# signal-a-2.net
KiCad netlist of a schematic drawn in EAGLE
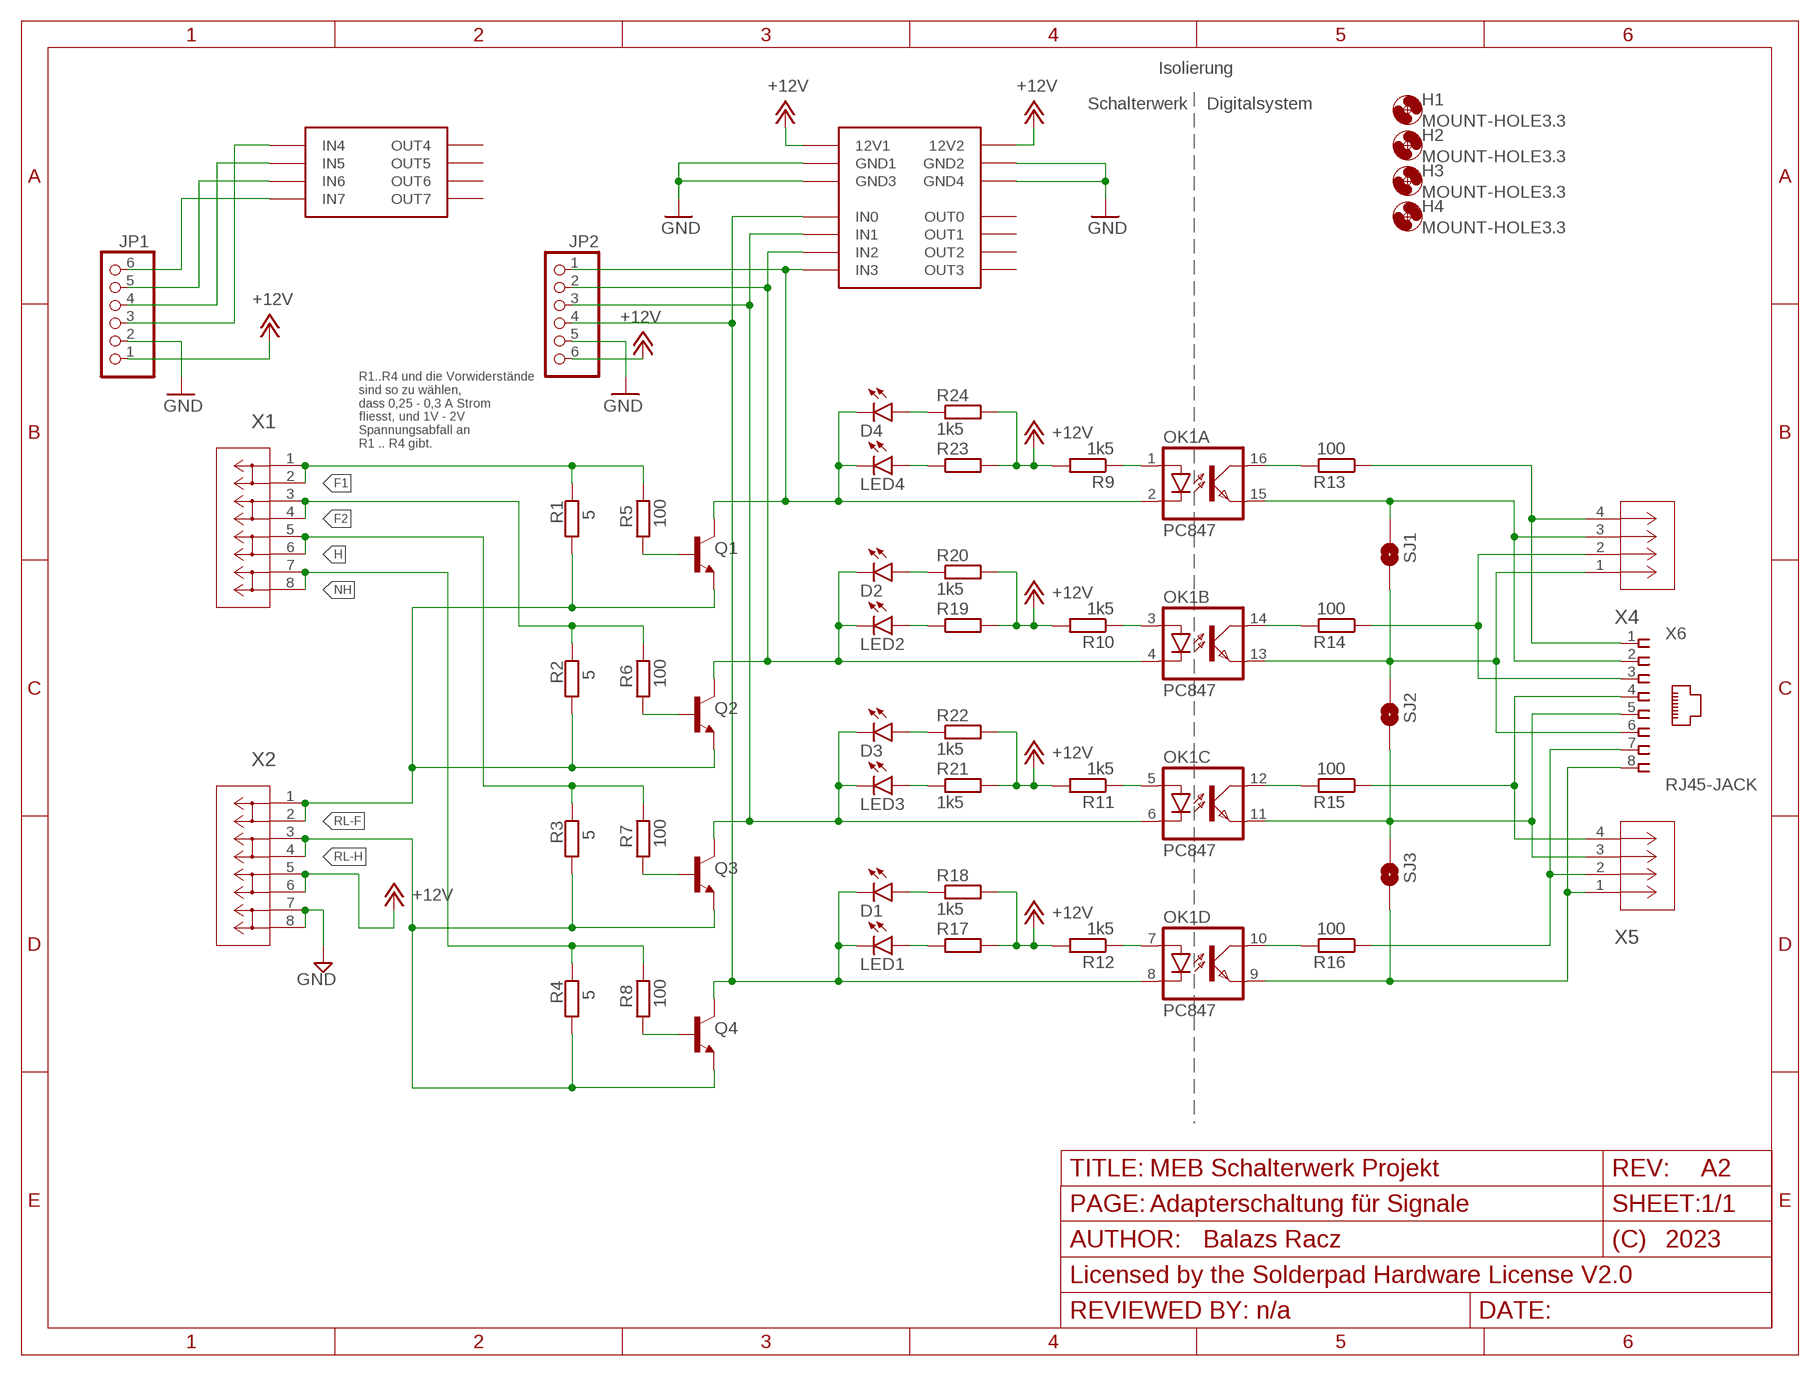
[diagram p0: schematic, sheet 1]

(export (version "E")
  (design (tool "Eeschema 10.0.6"))
  (components
    (comp (ref "D1")
      (value "LEDHEADER")
      (footprint "eagle-import:LEDHEADER")
      (libsource (lib "eagle-import") (part "LEDHEADER"))
    )
    (comp (ref "D2")
      (value "LEDHEADER")
      (footprint "eagle-import:LEDHEADER")
      (libsource (lib "eagle-import") (part "LEDHEADER"))
    )
    (comp (ref "D3")
      (value "LEDHEADER")
      (footprint "eagle-import:LEDHEADER")
      (libsource (lib "eagle-import") (part "LEDHEADER"))
    )
    (comp (ref "D4")
      (value "LEDHEADER")
      (footprint "eagle-import:LEDHEADER")
      (libsource (lib "eagle-import") (part "LEDHEADER"))
    )
    (comp (ref "H1")
      (value "MOUNT-HOLE3.3")
      (footprint "eagle-import:3,3")
      (libsource (lib "eagle-import") (part "MOUNT-HOLE3.3"))
    )
    (comp (ref "H2")
      (value "MOUNT-HOLE3.3")
      (footprint "eagle-import:3,3")
      (libsource (lib "eagle-import") (part "MOUNT-HOLE3.3"))
    )
    (comp (ref "H3")
      (value "MOUNT-HOLE3.3")
      (footprint "eagle-import:3,3")
      (libsource (lib "eagle-import") (part "MOUNT-HOLE3.3"))
    )
    (comp (ref "H4")
      (value "MOUNT-HOLE3.3")
      (footprint "eagle-import:3,3")
      (libsource (lib "eagle-import") (part "MOUNT-HOLE3.3"))
    )
    (comp (ref "JP1")
      (value "PINHD-1X6-EDGE")
      (footprint "eagle-import:1X06")
      (libsource (lib "eagle-import") (part "PINHD-1X6-EDGE"))
    )
    (comp (ref "JP2")
      (value "PINHD-1X6-EDGE")
      (footprint "eagle-import:1X06")
      (libsource (lib "eagle-import") (part "PINHD-1X6-EDGE"))
    )
    (comp (ref "LED1")
      (value "LEDCHIPLED_0603")
      (footprint "eagle-import:CHIPLED_0603")
      (libsource (lib "eagle-import") (part "LEDCHIPLED_0603"))
    )
    (comp (ref "LED2")
      (value "LEDCHIPLED_0603")
      (footprint "eagle-import:CHIPLED_0603")
      (libsource (lib "eagle-import") (part "LEDCHIPLED_0603"))
    )
    (comp (ref "LED3")
      (value "LEDCHIPLED_0603")
      (footprint "eagle-import:CHIPLED_0603")
      (libsource (lib "eagle-import") (part "LEDCHIPLED_0603"))
    )
    (comp (ref "LED4")
      (value "LEDCHIPLED_0603")
      (footprint "eagle-import:CHIPLED_0603")
      (libsource (lib "eagle-import") (part "LEDCHIPLED_0603"))
    )
    (comp (ref "OK1")
      (value "PC847")
      (footprint "eagle-import:DIL16")
      (libsource (lib "eagle-import") (part "PC847"))
    )
    (comp (ref "Q1")
      (value "NPN-23")
      (footprint "eagle-import:SOT23")
      (libsource (lib "eagle-import") (part "NPN-23"))
    )
    (comp (ref "Q2")
      (value "NPN-23")
      (footprint "eagle-import:SOT23")
      (libsource (lib "eagle-import") (part "NPN-23"))
    )
    (comp (ref "Q3")
      (value "NPN-23")
      (footprint "eagle-import:SOT23")
      (libsource (lib "eagle-import") (part "NPN-23"))
    )
    (comp (ref "Q4")
      (value "NPN-23")
      (footprint "eagle-import:SOT23")
      (libsource (lib "eagle-import") (part "NPN-23"))
    )
    (comp (ref "R1")
      (value "5")
      (footprint "eagle-import:0617_22")
      (libsource (lib "eagle-import") (part "R-EU_0617/22"))
    )
    (comp (ref "R2")
      (value "5")
      (footprint "eagle-import:0617_22")
      (libsource (lib "eagle-import") (part "R-EU_0617/22"))
    )
    (comp (ref "R3")
      (value "5")
      (footprint "eagle-import:0617_22")
      (libsource (lib "eagle-import") (part "R-EU_0617/22"))
    )
    (comp (ref "R4")
      (value "5")
      (footprint "eagle-import:0617_22")
      (libsource (lib "eagle-import") (part "R-EU_0617/22"))
    )
    (comp (ref "R5")
      (value "100")
      (footprint "eagle-import:R0805")
      (libsource (lib "eagle-import") (part "R-EU_R0805"))
    )
    (comp (ref "R6")
      (value "100")
      (footprint "eagle-import:R0805")
      (libsource (lib "eagle-import") (part "R-EU_R0805"))
    )
    (comp (ref "R7")
      (value "100")
      (footprint "eagle-import:R0805")
      (libsource (lib "eagle-import") (part "R-EU_R0805"))
    )
    (comp (ref "R8")
      (value "100")
      (footprint "eagle-import:R0805")
      (libsource (lib "eagle-import") (part "R-EU_R0805"))
    )
    (comp (ref "R9")
      (value "1k5")
      (footprint "eagle-import:R0805")
      (libsource (lib "eagle-import") (part "R-EU_R0805"))
    )
    (comp (ref "R10")
      (value "1k5")
      (footprint "eagle-import:R0805")
      (libsource (lib "eagle-import") (part "R-EU_R0805"))
    )
    (comp (ref "R11")
      (value "1k5")
      (footprint "eagle-import:R0805")
      (libsource (lib "eagle-import") (part "R-EU_R0805"))
    )
    (comp (ref "R12")
      (value "1k5")
      (footprint "eagle-import:R0805")
      (libsource (lib "eagle-import") (part "R-EU_R0805"))
    )
    (comp (ref "R13")
      (value "100")
      (footprint "eagle-import:R0805")
      (libsource (lib "eagle-import") (part "R-EU_R0805"))
    )
    (comp (ref "R14")
      (value "100")
      (footprint "eagle-import:R0805")
      (libsource (lib "eagle-import") (part "R-EU_R0805"))
    )
    (comp (ref "R15")
      (value "100")
      (footprint "eagle-import:R0805")
      (libsource (lib "eagle-import") (part "R-EU_R0805"))
    )
    (comp (ref "R16")
      (value "100")
      (footprint "eagle-import:R0805")
      (libsource (lib "eagle-import") (part "R-EU_R0805"))
    )
    (comp (ref "R17")
      (value "1k5")
      (footprint "eagle-import:R0805")
      (libsource (lib "eagle-import") (part "R-EU_R0805"))
    )
    (comp (ref "R18")
      (value "1k5")
      (footprint "eagle-import:R0805")
      (libsource (lib "eagle-import") (part "R-EU_R0805"))
    )
    (comp (ref "R19")
      (value "1k5")
      (footprint "eagle-import:R0805")
      (libsource (lib "eagle-import") (part "R-EU_R0805"))
    )
    (comp (ref "R20")
      (value "1k5")
      (footprint "eagle-import:R0805")
      (libsource (lib "eagle-import") (part "R-EU_R0805"))
    )
    (comp (ref "R21")
      (value "1k5")
      (footprint "eagle-import:R0805")
      (libsource (lib "eagle-import") (part "R-EU_R0805"))
    )
    (comp (ref "R22")
      (value "1k5")
      (footprint "eagle-import:R0805")
      (libsource (lib "eagle-import") (part "R-EU_R0805"))
    )
    (comp (ref "R23")
      (value "1k5")
      (footprint "eagle-import:R0805")
      (libsource (lib "eagle-import") (part "R-EU_R0805"))
    )
    (comp (ref "R24")
      (value "1k5")
      (footprint "eagle-import:R0805")
      (libsource (lib "eagle-import") (part "R-EU_R0805"))
    )
    (comp (ref "SJ1")
      (value "SJRND2")
      (footprint "eagle-import:SJ_RND2")
      (libsource (lib "eagle-import") (part "SJRND2"))
    )
    (comp (ref "SJ2")
      (value "SJRND2")
      (footprint "eagle-import:SJ_RND2")
      (libsource (lib "eagle-import") (part "SJRND2"))
    )
    (comp (ref "SJ3")
      (value "SJRND2")
      (footprint "eagle-import:SJ_RND2")
      (libsource (lib "eagle-import") (part "SJRND2"))
    )
    (comp (ref "X1")
      (value "PHNX_4P_508CONN_1017493")
      (footprint "eagle-import:PHNX_4P_508")
      (fields
        (field (name "MANUFACTURER_PART_NUMBER") "1017505")
        (field (name "COPYRIGHT") "Copyright (C) 2023 Ultra Librarian. All rights reserved.")
      )
      (libsource (lib "eagle-import") (part "PHNX_4P_508CONN_1017493"))
    )
    (comp (ref "X2")
      (value "PHNX_4P_508CONN_1017493")
      (footprint "eagle-import:PHNX_4P_508")
      (fields
        (field (name "MANUFACTURER_PART_NUMBER") "1017505")
        (field (name "COPYRIGHT") "Copyright (C) 2023 Ultra Librarian. All rights reserved.")
      )
      (libsource (lib "eagle-import") (part "PHNX_4P_508CONN_1017493"))
    )
    (comp (ref "X3")
      (value "IO-HAT")
      (footprint "eagle-import:IOBOARD")
      (libsource (lib "eagle-import") (part "IO-HAT"))
    )
    (comp (ref "X4")
      (value "PHNX_4P_350CONN_1984989_PXC")
      (footprint "eagle-import:PHNX_4P_350")
      (fields
        (field (name "MANUFACTURER_PART_NUMBER") "1984989")
        (field (name "COPYRIGHT") "Copyright (C) 2023 Ultra Librarian. All rights reserved.")
      )
      (libsource (lib "eagle-import") (part "PHNX_4P_350CONN_1984989_PXC"))
    )
    (comp (ref "X5")
      (value "PHNX_4P_350CONN_1984989_PXC")
      (footprint "eagle-import:PHNX_4P_350")
      (fields
        (field (name "MANUFACTURER_PART_NUMBER") "1984989")
        (field (name "COPYRIGHT") "Copyright (C) 2023 Ultra Librarian. All rights reserved.")
      )
      (libsource (lib "eagle-import") (part "PHNX_4P_350CONN_1984989_PXC"))
    )
    (comp (ref "X6")
      (value "RJ45-JACK")
      (footprint "eagle-import:RJ45-PULSE-E5J88")
      (libsource (lib "eagle-import") (part "RJ45-JACKRJ45-PULSE-E5J00"))
    )
  )
  (nets
    (net (code "1") (name "+12V") (class "Default")
      (node (ref "JP1") (pin "1") (pinfunction "1_1") (pintype "passive"))
      (node (ref "JP2") (pin "6") (pinfunction "6_6") (pintype "passive"))
      (node (ref "R10") (pin "2") (pinfunction "2_2") (pintype "passive"))
      (node (ref "R11") (pin "2") (pinfunction "2_2") (pintype "passive"))
      (node (ref "R12") (pin "2") (pinfunction "2_2") (pintype "passive"))
      (node (ref "R17") (pin "2") (pinfunction "2_2") (pintype "passive"))
      (node (ref "R18") (pin "2") (pinfunction "2_2") (pintype "passive"))
      (node (ref "R19") (pin "2") (pinfunction "2_2") (pintype "passive"))
      (node (ref "R20") (pin "2") (pinfunction "2_2") (pintype "passive"))
      (node (ref "R21") (pin "2") (pinfunction "2_2") (pintype "passive"))
      (node (ref "R22") (pin "2") (pinfunction "2_2") (pintype "passive"))
      (node (ref "R23") (pin "2") (pinfunction "2_2") (pintype "passive"))
      (node (ref "R24") (pin "2") (pinfunction "2_2") (pintype "passive"))
      (node (ref "R9") (pin "2") (pinfunction "2_2") (pintype "passive"))
      (node (ref "X2") (pin "5") (pinfunction "5_5") (pintype "passive"))
      (node (ref "X2") (pin "6") (pinfunction "6_6") (pintype "passive"))
      (node (ref "X3") (pin "P$1") (pinfunction "12V1_P$1") (pintype "power_in"))
      (node (ref "X3") (pin "P$22") (pinfunction "12V2_P$22") (pintype "power_in"))
    )
    (net (code "2") (name "F1") (class "Default")
      (node (ref "R1") (pin "1") (pinfunction "1_1") (pintype "passive"))
      (node (ref "R5") (pin "2") (pinfunction "2_2") (pintype "passive"))
      (node (ref "X1") (pin "1") (pinfunction "1_1") (pintype "passive"))
      (node (ref "X1") (pin "2") (pinfunction "2_2") (pintype "passive"))
    )
    (net (code "3") (name "F2") (class "Default")
      (node (ref "R2") (pin "1") (pinfunction "1_1") (pintype "passive"))
      (node (ref "R6") (pin "2") (pinfunction "2_2") (pintype "passive"))
      (node (ref "X1") (pin "3") (pinfunction "3_3") (pintype "passive"))
      (node (ref "X1") (pin "4") (pinfunction "4_4") (pintype "passive"))
    )
    (net (code "4") (name "GND") (class "Default")
      (node (ref "JP1") (pin "2") (pinfunction "2_2") (pintype "passive"))
      (node (ref "JP2") (pin "5") (pinfunction "5_5") (pintype "passive"))
      (node (ref "X2") (pin "7") (pinfunction "7_7") (pintype "passive"))
      (node (ref "X2") (pin "8") (pinfunction "8_8") (pintype "passive"))
      (node (ref "X3") (pin "P$11") (pinfunction "GND3_P$11") (pintype "power_in"))
      (node (ref "X3") (pin "P$12") (pinfunction "GND4_P$12") (pintype "power_in"))
      (node (ref "X3") (pin "P$2") (pinfunction "GND1_P$2") (pintype "power_in"))
      (node (ref "X3") (pin "P$21") (pinfunction "GND2_P$21") (pintype "power_in"))
    )
    (net (code "5") (name "H") (class "Default")
      (node (ref "R3") (pin "1") (pinfunction "1_1") (pintype "passive"))
      (node (ref "R7") (pin "2") (pinfunction "2_2") (pintype "passive"))
      (node (ref "X1") (pin "5") (pinfunction "5_5") (pintype "passive"))
      (node (ref "X1") (pin "6") (pinfunction "6_6") (pintype "passive"))
    )
    (net (code "6") (name "NH") (class "Default")
      (node (ref "R4") (pin "1") (pinfunction "1_1") (pintype "passive"))
      (node (ref "R8") (pin "2") (pinfunction "2_2") (pintype "passive"))
      (node (ref "X1") (pin "7") (pinfunction "7_7") (pintype "passive"))
      (node (ref "X1") (pin "8") (pinfunction "8_8") (pintype "passive"))
    )
    (net (code "7") (name "Net-(D1-PadA)") (class "Default")
      (node (ref "D1") (pin "A") (pinfunction "A_A") (pintype "passive"))
      (node (ref "R18") (pin "1") (pinfunction "1_1") (pintype "passive"))
    )
    (net (code "8") (name "Net-(D2-PadA)") (class "Default")
      (node (ref "D2") (pin "A") (pinfunction "A_A") (pintype "passive"))
      (node (ref "R20") (pin "1") (pinfunction "1_1") (pintype "passive"))
    )
    (net (code "9") (name "Net-(D3-PadA)") (class "Default")
      (node (ref "D3") (pin "A") (pinfunction "A_A") (pintype "passive"))
      (node (ref "R22") (pin "1") (pinfunction "1_1") (pintype "passive"))
    )
    (net (code "10") (name "Net-(D4-PadA)") (class "Default")
      (node (ref "D4") (pin "A") (pinfunction "A_A") (pintype "passive"))
      (node (ref "R24") (pin "1") (pinfunction "1_1") (pintype "passive"))
    )
    (net (code "11") (name "Net-(LED1-PadA)") (class "Default")
      (node (ref "LED1") (pin "A") (pinfunction "A_A") (pintype "passive"))
      (node (ref "R17") (pin "1") (pinfunction "1_1") (pintype "passive"))
    )
    (net (code "12") (name "Net-(LED2-PadA)") (class "Default")
      (node (ref "LED2") (pin "A") (pinfunction "A_A") (pintype "passive"))
      (node (ref "R19") (pin "1") (pinfunction "1_1") (pintype "passive"))
    )
    (net (code "13") (name "Net-(LED3-PadA)") (class "Default")
      (node (ref "LED3") (pin "A") (pinfunction "A_A") (pintype "passive"))
      (node (ref "R21") (pin "1") (pinfunction "1_1") (pintype "passive"))
    )
    (net (code "14") (name "Net-(LED4-PadA)") (class "Default")
      (node (ref "LED4") (pin "A") (pinfunction "A_A") (pintype "passive"))
      (node (ref "R23") (pin "1") (pinfunction "1_1") (pintype "passive"))
    )
    (net (code "15") (name "Net-(OK1A-A)") (class "Default")
      (node (ref "OK1") (pin "1") (pinfunction "A_1") (pintype "passive"))
      (node (ref "R9") (pin "1") (pinfunction "1_1") (pintype "passive"))
    )
    (net (code "16") (name "Net-(OK1A-C)") (class "Default")
      (node (ref "D4") (pin "C") (pinfunction "C_C") (pintype "passive"))
      (node (ref "JP2") (pin "1") (pinfunction "1_1") (pintype "passive"))
      (node (ref "LED4") (pin "C") (pinfunction "C_C") (pintype "passive"))
      (node (ref "OK1") (pin "2") (pinfunction "C_2") (pintype "passive"))
      (node (ref "Q1") (pin "3") (pinfunction "C_3") (pintype "passive"))
      (node (ref "X3") (pin "P$6") (pinfunction "IN3_P$6") (pintype "input"))
    )
    (net (code "17") (name "Net-(OK1A-COL)") (class "Default")
      (node (ref "OK1") (pin "16") (pinfunction "COL_16") (pintype "passive"))
      (node (ref "R13") (pin "2") (pinfunction "2_2") (pintype "passive"))
    )
    (net (code "18") (name "Net-(OK1A-EMIT)") (class "Default")
      (node (ref "OK1") (pin "15") (pinfunction "EMIT_15") (pintype "passive"))
      (node (ref "SJ1") (pin "P$2") (pinfunction "2_P$2") (pintype "passive"))
      (node (ref "X4") (pin "3") (pinfunction "3_3") (pintype "passive"))
      (node (ref "X6") (pin "2") (pinfunction "2_2") (pintype "passive"))
    )
    (net (code "19") (name "Net-(OK1B-A)") (class "Default")
      (node (ref "OK1") (pin "3") (pinfunction "A_3") (pintype "passive"))
      (node (ref "R10") (pin "1") (pinfunction "1_1") (pintype "passive"))
    )
    (net (code "20") (name "Net-(OK1B-C)") (class "Default")
      (node (ref "D2") (pin "C") (pinfunction "C_C") (pintype "passive"))
      (node (ref "JP2") (pin "2") (pinfunction "2_2") (pintype "passive"))
      (node (ref "LED2") (pin "C") (pinfunction "C_C") (pintype "passive"))
      (node (ref "OK1") (pin "4") (pinfunction "C_4") (pintype "passive"))
      (node (ref "Q2") (pin "3") (pinfunction "C_3") (pintype "passive"))
      (node (ref "X3") (pin "P$5") (pinfunction "IN2_P$5") (pintype "input"))
    )
    (net (code "21") (name "Net-(OK1B-COL)") (class "Default")
      (node (ref "OK1") (pin "14") (pinfunction "COL_14") (pintype "passive"))
      (node (ref "R14") (pin "2") (pinfunction "2_2") (pintype "passive"))
    )
    (net (code "22") (name "Net-(OK1B-EMIT)") (class "Default")
      (node (ref "OK1") (pin "13") (pinfunction "EMIT_13") (pintype "passive"))
      (node (ref "SJ1") (pin "P$1") (pinfunction "1_P$1") (pintype "passive"))
      (node (ref "SJ2") (pin "P$2") (pinfunction "2_P$2") (pintype "passive"))
      (node (ref "X4") (pin "1") (pinfunction "1_1") (pintype "passive"))
      (node (ref "X6") (pin "6") (pinfunction "6_6") (pintype "passive"))
    )
    (net (code "23") (name "Net-(OK1C-A)") (class "Default")
      (node (ref "OK1") (pin "5") (pinfunction "A_5") (pintype "passive"))
      (node (ref "R11") (pin "1") (pinfunction "1_1") (pintype "passive"))
    )
    (net (code "24") (name "Net-(OK1C-C)") (class "Default")
      (node (ref "D3") (pin "C") (pinfunction "C_C") (pintype "passive"))
      (node (ref "JP2") (pin "3") (pinfunction "3_3") (pintype "passive"))
      (node (ref "LED3") (pin "C") (pinfunction "C_C") (pintype "passive"))
      (node (ref "OK1") (pin "6") (pinfunction "C_6") (pintype "passive"))
      (node (ref "Q3") (pin "3") (pinfunction "C_3") (pintype "passive"))
      (node (ref "X3") (pin "P$4") (pinfunction "IN1_P$4") (pintype "input"))
    )
    (net (code "25") (name "Net-(OK1C-COL)") (class "Default")
      (node (ref "OK1") (pin "12") (pinfunction "COL_12") (pintype "passive"))
      (node (ref "R15") (pin "2") (pinfunction "2_2") (pintype "passive"))
    )
    (net (code "26") (name "Net-(OK1C-EMIT)") (class "Default")
      (node (ref "OK1") (pin "11") (pinfunction "EMIT_11") (pintype "passive"))
      (node (ref "SJ2") (pin "P$1") (pinfunction "1_P$1") (pintype "passive"))
      (node (ref "SJ3") (pin "P$2") (pinfunction "2_P$2") (pintype "passive"))
      (node (ref "X5") (pin "3") (pinfunction "3_3") (pintype "passive"))
      (node (ref "X6") (pin "5") (pinfunction "5_5") (pintype "passive"))
    )
    (net (code "27") (name "Net-(OK1D-A)") (class "Default")
      (node (ref "OK1") (pin "7") (pinfunction "A_7") (pintype "passive"))
      (node (ref "R12") (pin "1") (pinfunction "1_1") (pintype "passive"))
    )
    (net (code "28") (name "Net-(OK1D-C)") (class "Default")
      (node (ref "D1") (pin "C") (pinfunction "C_C") (pintype "passive"))
      (node (ref "JP2") (pin "4") (pinfunction "4_4") (pintype "passive"))
      (node (ref "LED1") (pin "C") (pinfunction "C_C") (pintype "passive"))
      (node (ref "OK1") (pin "8") (pinfunction "C_8") (pintype "passive"))
      (node (ref "Q4") (pin "3") (pinfunction "C_3") (pintype "passive"))
      (node (ref "X3") (pin "P$3") (pinfunction "IN0_P$3") (pintype "input"))
    )
    (net (code "29") (name "Net-(OK1D-COL)") (class "Default")
      (node (ref "OK1") (pin "10") (pinfunction "COL_10") (pintype "passive"))
      (node (ref "R16") (pin "2") (pinfunction "2_2") (pintype "passive"))
    )
    (net (code "30") (name "Net-(OK1D-EMIT)") (class "Default")
      (node (ref "OK1") (pin "9") (pinfunction "EMIT_9") (pintype "passive"))
      (node (ref "SJ3") (pin "P$1") (pinfunction "1_P$1") (pintype "passive"))
      (node (ref "X5") (pin "1") (pinfunction "1_1") (pintype "passive"))
      (node (ref "X6") (pin "8") (pinfunction "8_8") (pintype "passive"))
    )
    (net (code "31") (name "Net-(Q1-B)") (class "Default")
      (node (ref "Q1") (pin "1") (pinfunction "B_1") (pintype "passive"))
      (node (ref "R5") (pin "1") (pinfunction "1_1") (pintype "passive"))
    )
    (net (code "32") (name "Net-(Q2-B)") (class "Default")
      (node (ref "Q2") (pin "1") (pinfunction "B_1") (pintype "passive"))
      (node (ref "R6") (pin "1") (pinfunction "1_1") (pintype "passive"))
    )
    (net (code "33") (name "Net-(Q3-B)") (class "Default")
      (node (ref "Q3") (pin "1") (pinfunction "B_1") (pintype "passive"))
      (node (ref "R7") (pin "1") (pinfunction "1_1") (pintype "passive"))
    )
    (net (code "34") (name "Net-(Q4-B)") (class "Default")
      (node (ref "Q4") (pin "1") (pinfunction "B_1") (pintype "passive"))
      (node (ref "R8") (pin "1") (pinfunction "1_1") (pintype "passive"))
    )
    (net (code "35") (name "Net-(R13-Pad1)") (class "Default")
      (node (ref "R13") (pin "1") (pinfunction "1_1") (pintype "passive"))
      (node (ref "X4") (pin "4") (pinfunction "4_4") (pintype "passive"))
      (node (ref "X6") (pin "1") (pinfunction "1_1") (pintype "passive"))
    )
    (net (code "36") (name "Net-(R14-Pad1)") (class "Default")
      (node (ref "R14") (pin "1") (pinfunction "1_1") (pintype "passive"))
      (node (ref "X4") (pin "2") (pinfunction "2_2") (pintype "passive"))
      (node (ref "X6") (pin "3") (pinfunction "3_3") (pintype "passive"))
    )
    (net (code "37") (name "Net-(R15-Pad1)") (class "Default")
      (node (ref "R15") (pin "1") (pinfunction "1_1") (pintype "passive"))
      (node (ref "X5") (pin "4") (pinfunction "4_4") (pintype "passive"))
      (node (ref "X6") (pin "4") (pinfunction "4_4") (pintype "passive"))
    )
    (net (code "38") (name "Net-(R16-Pad1)") (class "Default")
      (node (ref "R16") (pin "1") (pinfunction "1_1") (pintype "passive"))
      (node (ref "X5") (pin "2") (pinfunction "2_2") (pintype "passive"))
      (node (ref "X6") (pin "7") (pinfunction "7_7") (pintype "passive"))
    )
    (net (code "39") (name "Net-(X3B-IN4)") (class "Default")
      (node (ref "JP1") (pin "3") (pinfunction "3_3") (pintype "passive"))
      (node (ref "X3") (pin "P$7") (pinfunction "IN4_P$7") (pintype "input"))
    )
    (net (code "40") (name "Net-(X3B-IN5)") (class "Default")
      (node (ref "JP1") (pin "4") (pinfunction "4_4") (pintype "passive"))
      (node (ref "X3") (pin "P$8") (pinfunction "IN5_P$8") (pintype "input"))
    )
    (net (code "41") (name "Net-(X3B-IN6)") (class "Default")
      (node (ref "JP1") (pin "5") (pinfunction "5_5") (pintype "passive"))
      (node (ref "X3") (pin "P$9") (pinfunction "IN6_P$9") (pintype "input"))
    )
    (net (code "42") (name "Net-(X3B-IN7)") (class "Default")
      (node (ref "JP1") (pin "6") (pinfunction "6_6") (pintype "passive"))
      (node (ref "X3") (pin "P$10") (pinfunction "IN7_P$10") (pintype "input"))
    )
    (net (code "43") (name "RL-F") (class "Default")
      (node (ref "Q1") (pin "2") (pinfunction "E_2") (pintype "passive"))
      (node (ref "Q2") (pin "2") (pinfunction "E_2") (pintype "passive"))
      (node (ref "R1") (pin "2") (pinfunction "2_2") (pintype "passive"))
      (node (ref "R2") (pin "2") (pinfunction "2_2") (pintype "passive"))
      (node (ref "X2") (pin "1") (pinfunction "1_1") (pintype "passive"))
      (node (ref "X2") (pin "2") (pinfunction "2_2") (pintype "passive"))
    )
    (net (code "44") (name "RL-H") (class "Default")
      (node (ref "Q3") (pin "2") (pinfunction "E_2") (pintype "passive"))
      (node (ref "Q4") (pin "2") (pinfunction "E_2") (pintype "passive"))
      (node (ref "R3") (pin "2") (pinfunction "2_2") (pintype "passive"))
      (node (ref "R4") (pin "2") (pinfunction "2_2") (pintype "passive"))
      (node (ref "X2") (pin "3") (pinfunction "3_3") (pintype "passive"))
      (node (ref "X2") (pin "4") (pinfunction "4_4") (pintype "passive"))
    )
    (net (code "45") (name "unconnected-(X3A-OUT0-PadP$20)") (class "Default")
      (node (ref "X3") (pin "P$20") (pinfunction "OUT0_P$20") (pintype "open_collector"))
    )
    (net (code "46") (name "unconnected-(X3A-OUT1-PadP$19)") (class "Default")
      (node (ref "X3") (pin "P$19") (pinfunction "OUT1_P$19") (pintype "open_collector"))
    )
    (net (code "47") (name "unconnected-(X3A-OUT2-PadP$18)") (class "Default")
      (node (ref "X3") (pin "P$18") (pinfunction "OUT2_P$18") (pintype "open_collector"))
    )
    (net (code "48") (name "unconnected-(X3A-OUT3-PadP$17)") (class "Default")
      (node (ref "X3") (pin "P$17") (pinfunction "OUT3_P$17") (pintype "open_collector"))
    )
    (net (code "49") (name "unconnected-(X3B-OUT4-PadP$16)") (class "Default")
      (node (ref "X3") (pin "P$16") (pinfunction "OUT4_P$16") (pintype "open_collector"))
    )
    (net (code "50") (name "unconnected-(X3B-OUT5-PadP$15)") (class "Default")
      (node (ref "X3") (pin "P$15") (pinfunction "OUT5_P$15") (pintype "open_collector"))
    )
    (net (code "51") (name "unconnected-(X3B-OUT6-PadP$14)") (class "Default")
      (node (ref "X3") (pin "P$14") (pinfunction "OUT6_P$14") (pintype "open_collector"))
    )
    (net (code "52") (name "unconnected-(X3B-OUT7-PadP$13)") (class "Default")
      (node (ref "X3") (pin "P$13") (pinfunction "OUT7_P$13") (pintype "open_collector"))
    )
  )
)
